# pulseox-v1.net
KiCad netlist of a schematic drawn in EAGLE
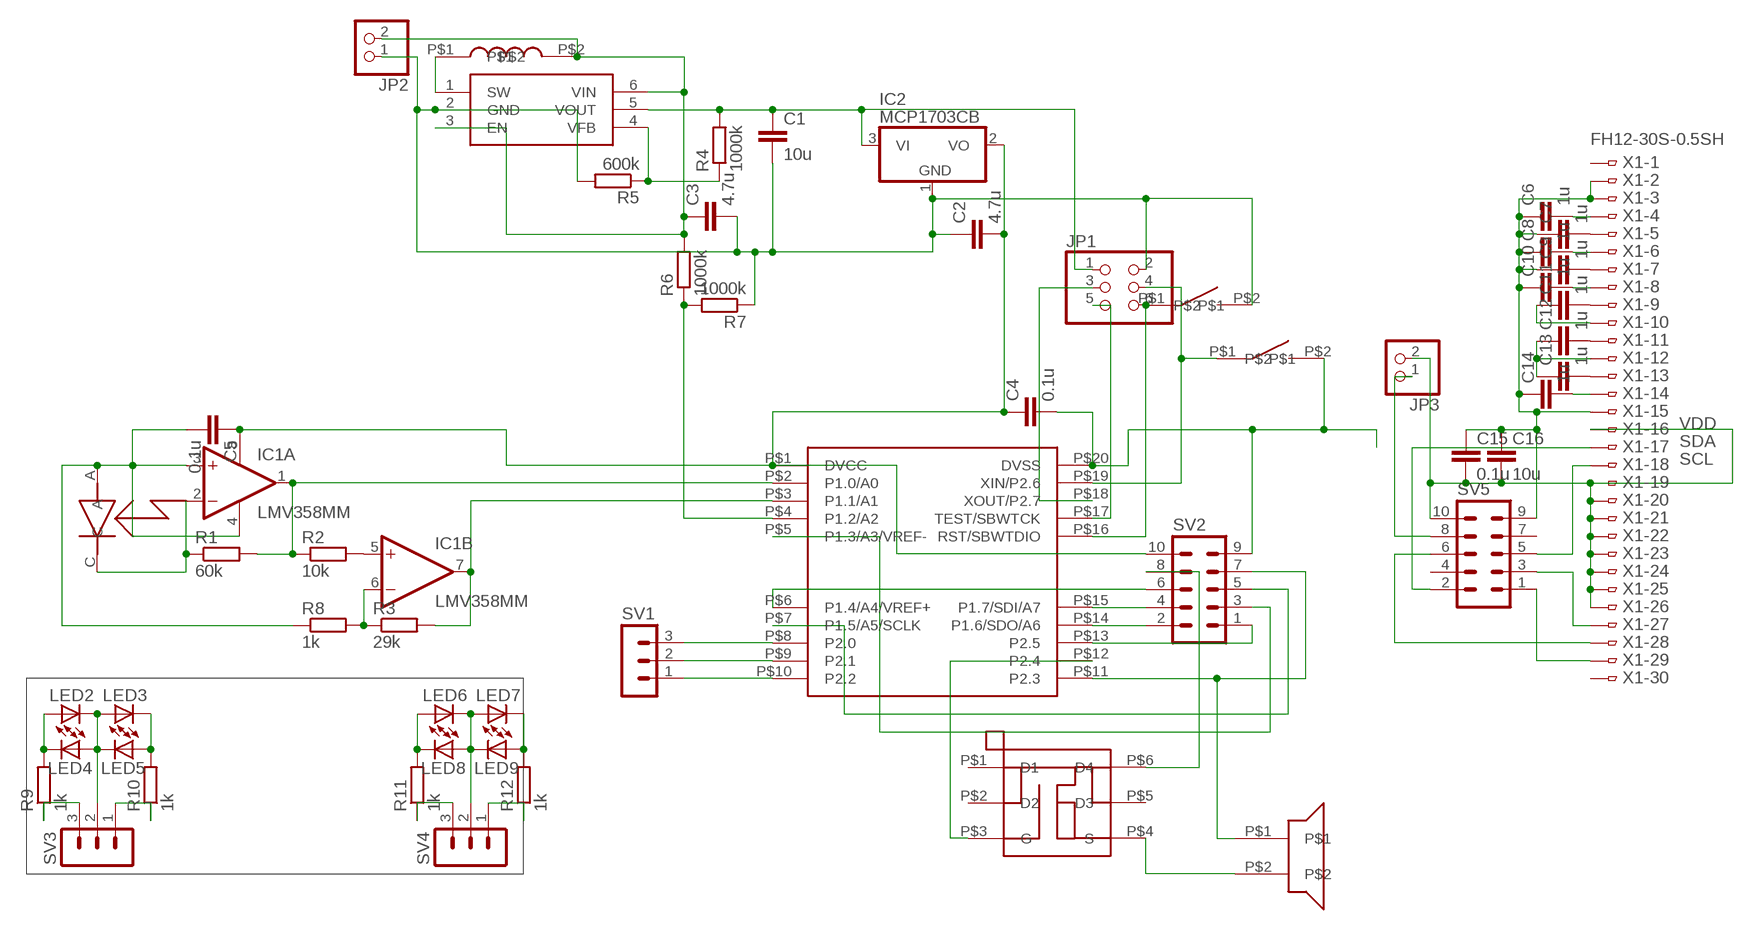
[diagram p0: schematic, sheet 1]

(export (version "E")
  (design (tool "Eeschema 10.0.6"))
  (components
    (comp (ref "C1")
      (value "10u")
      (footprint "eagle-import:C0603K")
      (libsource (lib "eagle-import") (part "C-EUC0603K"))
    )
    (comp (ref "C2")
      (value "4.7u")
      (footprint "eagle-import:C0603K")
      (libsource (lib "eagle-import") (part "C-EUC0603K"))
    )
    (comp (ref "C3")
      (value "4.7u")
      (footprint "eagle-import:C0603K")
      (libsource (lib "eagle-import") (part "C-EUC0603K"))
    )
    (comp (ref "C4")
      (value "0.1u")
      (footprint "eagle-import:C0603K")
      (libsource (lib "eagle-import") (part "C-EUC0603K"))
    )
    (comp (ref "C5")
      (value "0.1u")
      (footprint "eagle-import:C0603K")
      (libsource (lib "eagle-import") (part "C-EUC0603K"))
    )
    (comp (ref "C6")
      (value "1u")
      (footprint "eagle-import:C0603K")
      (libsource (lib "eagle-import") (part "C-EUC0603K"))
    )
    (comp (ref "C7")
      (value "1u")
      (footprint "eagle-import:C0603K")
      (libsource (lib "eagle-import") (part "C-EUC0603K"))
    )
    (comp (ref "C8")
      (value "1u")
      (footprint "eagle-import:C0603K")
      (libsource (lib "eagle-import") (part "C-EUC0603K"))
    )
    (comp (ref "C9")
      (value "1u")
      (footprint "eagle-import:C0603K")
      (libsource (lib "eagle-import") (part "C-EUC0603K"))
    )
    (comp (ref "C10")
      (value "1u")
      (footprint "eagle-import:C0603K")
      (libsource (lib "eagle-import") (part "C-EUC0603K"))
    )
    (comp (ref "C11")
      (value "1u")
      (footprint "eagle-import:C0603K")
      (libsource (lib "eagle-import") (part "C-EUC0603K"))
    )
    (comp (ref "C12")
      (value "1u")
      (footprint "eagle-import:C0603K")
      (libsource (lib "eagle-import") (part "C-EUC0603K"))
    )
    (comp (ref "C13")
      (value "1u")
      (footprint "eagle-import:C0603K")
      (libsource (lib "eagle-import") (part "C-EUC0603K"))
    )
    (comp (ref "C14")
      (value "1u")
      (footprint "eagle-import:C0603K")
      (libsource (lib "eagle-import") (part "C-EUC0603K"))
    )
    (comp (ref "C15")
      (value "0.1u")
      (footprint "eagle-import:C0603K")
      (libsource (lib "eagle-import") (part "C-EUC0603K"))
    )
    (comp (ref "C16")
      (value "10u")
      (footprint "eagle-import:C0603K")
      (libsource (lib "eagle-import") (part "C-EUC0603K"))
    )
    (comp (ref "IC1")
      (value "LMV358MM")
      (footprint "eagle-import:MSOP08")
      (libsource (lib "eagle-import") (part "LMV358?MM"))
    )
    (comp (ref "IC2")
      (value "MCP1703CB")
      (footprint "eagle-import:SOT23")
      (libsource (lib "eagle-import") (part "MCP1703CB"))
    )
    (comp (ref "JP1")
      (value "PINHD-2X3")
      (footprint "eagle-import:2X03")
      (libsource (lib "eagle-import") (part "PINHD-2X3"))
    )
    (comp (ref "JP2")
      (value "PINHD-1X2")
      (footprint "eagle-import:1X02")
      (libsource (lib "eagle-import") (part "PINHD-1X2"))
    )
    (comp (ref "JP3")
      (value "PINHD-1X2")
      (footprint "eagle-import:1X02")
      (libsource (lib "eagle-import") (part "PINHD-1X2"))
    )
    (comp (ref "LED1")
      (value "QSB34ZR")
      (footprint "eagle-import:R-PLCC2")
      (libsource (lib "eagle-import") (part "QSB34ZR"))
    )
    (comp (ref "LED2")
      (value "LEDCHIP-LED0603")
      (footprint "eagle-import:CHIP-LED0603")
      (libsource (lib "eagle-import") (part "LEDCHIP-LED0603"))
    )
    (comp (ref "LED3")
      (value "LEDCHIP-LED0603")
      (footprint "eagle-import:CHIP-LED0603")
      (libsource (lib "eagle-import") (part "LEDCHIP-LED0603"))
    )
    (comp (ref "LED4")
      (value "LEDCHIP-LED0603")
      (footprint "eagle-import:CHIP-LED0603")
      (libsource (lib "eagle-import") (part "LEDCHIP-LED0603"))
    )
    (comp (ref "LED5")
      (value "LEDCHIP-LED0603")
      (footprint "eagle-import:CHIP-LED0603")
      (libsource (lib "eagle-import") (part "LEDCHIP-LED0603"))
    )
    (comp (ref "LED6")
      (value "LEDCHIP-LED0603")
      (footprint "eagle-import:CHIP-LED0603")
      (libsource (lib "eagle-import") (part "LEDCHIP-LED0603"))
    )
    (comp (ref "LED7")
      (value "LEDCHIP-LED0603")
      (footprint "eagle-import:CHIP-LED0603")
      (libsource (lib "eagle-import") (part "LEDCHIP-LED0603"))
    )
    (comp (ref "LED8")
      (value "LEDCHIP-LED0603")
      (footprint "eagle-import:CHIP-LED0603")
      (libsource (lib "eagle-import") (part "LEDCHIP-LED0603"))
    )
    (comp (ref "LED9")
      (value "LEDCHIP-LED0603")
      (footprint "eagle-import:CHIP-LED0603")
      (libsource (lib "eagle-import") (part "LEDCHIP-LED0603"))
    )
    (comp (ref "R1")
      (value "60k")
      (footprint "eagle-import:R0603")
      (libsource (lib "eagle-import") (part "R-EU_R0603"))
    )
    (comp (ref "R2")
      (value "10k")
      (footprint "eagle-import:R0603")
      (libsource (lib "eagle-import") (part "R-EU_R0603"))
    )
    (comp (ref "R3")
      (value "29k")
      (footprint "eagle-import:R0603")
      (libsource (lib "eagle-import") (part "R-EU_R0603"))
    )
    (comp (ref "R4")
      (value "1000k")
      (footprint "eagle-import:R0603")
      (libsource (lib "eagle-import") (part "R-EU_R0603"))
    )
    (comp (ref "R5")
      (value "600k")
      (footprint "eagle-import:R0603")
      (libsource (lib "eagle-import") (part "R-EU_R0603"))
    )
    (comp (ref "R6")
      (value "1000k")
      (footprint "eagle-import:R0603")
      (libsource (lib "eagle-import") (part "R-EU_R0603"))
    )
    (comp (ref "R7")
      (value "1000k")
      (footprint "eagle-import:R0603")
      (libsource (lib "eagle-import") (part "R-EU_R0603"))
    )
    (comp (ref "R8")
      (value "1k")
      (footprint "eagle-import:R0603")
      (libsource (lib "eagle-import") (part "R-EU_R0603"))
    )
    (comp (ref "R9")
      (value "1k")
      (footprint "eagle-import:R0603")
      (libsource (lib "eagle-import") (part "R-EU_R0603"))
    )
    (comp (ref "R10")
      (value "1k")
      (footprint "eagle-import:R0603")
      (libsource (lib "eagle-import") (part "R-EU_R0603"))
    )
    (comp (ref "R11")
      (value "1k")
      (footprint "eagle-import:R0603")
      (libsource (lib "eagle-import") (part "R-EU_R0603"))
    )
    (comp (ref "R12")
      (value "1k")
      (footprint "eagle-import:R0603")
      (libsource (lib "eagle-import") (part "R-EU_R0603"))
    )
    (comp (ref "SV1")
      (value "MA03-1")
      (footprint "eagle-import:MA03-1")
      (libsource (lib "eagle-import") (part "MA03-1"))
    )
    (comp (ref "SV2")
      (value "MA05-2")
      (footprint "eagle-import:MA05-2")
      (libsource (lib "eagle-import") (part "MA05-2"))
    )
    (comp (ref "SV3")
      (value "MA03-1")
      (footprint "eagle-import:MA03-1")
      (libsource (lib "eagle-import") (part "MA03-1"))
    )
    (comp (ref "SV4")
      (value "MA03-1")
      (footprint "eagle-import:MA03-1")
      (libsource (lib "eagle-import") (part "MA03-1"))
    )
    (comp (ref "SV5")
      (value "MA05-2")
      (footprint "eagle-import:MA05-2")
      (libsource (lib "eagle-import") (part "MA05-2"))
    )
    (comp (ref "U$1")
      (value "MSP430G2452IPW20")
      (footprint "eagle-import:TSSOP-20")
      (libsource (lib "eagle-import") (part "MSP430G2452IPW20"))
    )
    (comp (ref "U$2")
      (value "MCP1640SOT23-6")
      (footprint "eagle-import:SOT23-6L")
      (libsource (lib "eagle-import") (part "MCP1640SOT23-6"))
    )
    (comp (ref "U$3")
      (value "WE-TPC")
      (footprint "eagle-import:WE-TPC")
      (libsource (lib "eagle-import") (part "WE-TPC"))
    )
    (comp (ref "U$4")
      (value "BSD816SN")
      (footprint "eagle-import:SOT363")
      (libsource (lib "eagle-import") (part "BSD816SN"))
    )
    (comp (ref "U$5")
      (value "FSMSM")
      (footprint "eagle-import:FSMSM")
      (libsource (lib "eagle-import") (part "FSMSM"))
    )
    (comp (ref "U$6")
      (value "FSMSM")
      (footprint "eagle-import:FSMSM")
      (libsource (lib "eagle-import") (part "FSMSM"))
    )
    (comp (ref "U$7")
      (value "AT-2440-TWT-R")
      (footprint "eagle-import:AT-2440-TWT-R")
      (libsource (lib "eagle-import") (part "AT-2440-TWT-R"))
    )
    (comp (ref "X1")
      (value "FH12-30S-0.5SH")
      (footprint "eagle-import:FH12-30S-0.5SH")
      (fields (field (name "MPN") "FH12-30S-0.5SH(55)"))
      (libsource (lib "eagle-import") (part "FH12-30S-0.5SH"))
    )
  )
  (nets
    (net (code "1") (name "/GND") (class "Default")
      (node (ref "C1") (pin "2") (pinfunction "2_2") (pintype "passive"))
      (node (ref "C2") (pin "1") (pinfunction "1_1") (pintype "passive"))
      (node (ref "C3") (pin "2") (pinfunction "2_2") (pintype "passive"))
      (node (ref "C4") (pin "2") (pinfunction "2_2") (pintype "passive"))
      (node (ref "C5") (pin "2") (pinfunction "2_2") (pintype "passive"))
      (node (ref "IC1") (pin "3") (pinfunction "+IN_3") (pintype "input"))
      (node (ref "IC1") (pin "4") (pinfunction "V-_4") (pintype "power_in"))
      (node (ref "IC2") (pin "1") (pinfunction "GND_1") (pintype "passive"))
      (node (ref "JP1") (pin "2") (pinfunction "2_2") (pintype "passive"))
      (node (ref "JP2") (pin "1") (pinfunction "1_1") (pintype "passive"))
      (node (ref "LED1") (pin "A") (pinfunction "A_A") (pintype "bidirectional"))
      (node (ref "R5") (pin "2") (pinfunction "2_2") (pintype "passive"))
      (node (ref "R7") (pin "1") (pinfunction "1_1") (pintype "passive"))
      (node (ref "R8") (pin "1") (pinfunction "1_1") (pintype "passive"))
      (node (ref "SV2") (pin "9") (pinfunction "9_9") (pintype "passive"))
      (node (ref "U$1") (pin "P$20") (pinfunction "DVSS_P$20") (pintype "bidirectional"))
      (node (ref "U$2") (pin "2") (pinfunction "GND_2") (pintype "bidirectional"))
      (node (ref "U$4") (pin "P$4") (pinfunction "S_P$4") (pintype "bidirectional"))
      (node (ref "U$5") (pin "P$2") (pinfunction "P$2_P$2") (pintype "bidirectional"))
      (node (ref "U$6") (pin "P$2") (pinfunction "P$2_P$2") (pintype "bidirectional"))
      (node (ref "U$7") (pin "P$2") (pinfunction "P$2_P$2") (pintype "bidirectional"))
    )
    (net (code "2") (name "Net-(IC1A--IN)") (class "Default")
      (node (ref "IC1") (pin "2") (pinfunction "-IN_2") (pintype "input"))
      (node (ref "LED1") (pin "C") (pinfunction "C_C") (pintype "bidirectional"))
      (node (ref "R1") (pin "1") (pinfunction "1_1") (pintype "passive"))
    )
    (net (code "3") (name "Net-(IC1A-OUT)") (class "Default")
      (node (ref "IC1") (pin "1") (pinfunction "OUT_1") (pintype "output"))
      (node (ref "R1") (pin "2") (pinfunction "2_2") (pintype "passive"))
      (node (ref "R2") (pin "1") (pinfunction "1_1") (pintype "passive"))
      (node (ref "U$1") (pin "P$2") (pinfunction "P1.0/A0_P$2") (pintype "bidirectional"))
    )
    (net (code "4") (name "Net-(IC1B-+IN)") (class "Default")
      (node (ref "IC1") (pin "5") (pinfunction "+IN_5") (pintype "input"))
      (node (ref "R2") (pin "2") (pinfunction "2_2") (pintype "passive"))
    )
    (net (code "5") (name "Net-(IC1B--IN)") (class "Default")
      (node (ref "IC1") (pin "6") (pinfunction "-IN_6") (pintype "input"))
      (node (ref "R3") (pin "1") (pinfunction "1_1") (pintype "passive"))
      (node (ref "R8") (pin "2") (pinfunction "2_2") (pintype "passive"))
    )
    (net (code "6") (name "Net-(IC1B-OUT)") (class "Default")
      (node (ref "IC1") (pin "7") (pinfunction "OUT_7") (pintype "output"))
      (node (ref "R3") (pin "2") (pinfunction "2_2") (pintype "passive"))
      (node (ref "U$1") (pin "P$3") (pinfunction "P1.1/A1_P$3") (pintype "bidirectional"))
    )
    (net (code "7") (name "Net-(IC1C-V+)") (class "Default")
      (node (ref "C2") (pin "2") (pinfunction "2_2") (pintype "passive"))
      (node (ref "C4") (pin "1") (pinfunction "1_1") (pintype "passive"))
      (node (ref "C5") (pin "1") (pinfunction "1_1") (pintype "passive"))
      (node (ref "IC1") (pin "8") (pinfunction "V+_8") (pintype "power_in"))
      (node (ref "IC2") (pin "2") (pinfunction "VO_2") (pintype "passive"))
      (node (ref "SV2") (pin "10") (pinfunction "10_10") (pintype "passive"))
      (node (ref "U$1") (pin "P$1") (pinfunction "DVCC_P$1") (pintype "bidirectional"))
    )
    (net (code "8") (name "Net-(IC2-VI)") (class "Default")
      (node (ref "C1") (pin "1") (pinfunction "1_1") (pintype "passive"))
      (node (ref "IC2") (pin "3") (pinfunction "VI_3") (pintype "input"))
      (node (ref "JP1") (pin "1") (pinfunction "1_1") (pintype "passive"))
      (node (ref "R4") (pin "2") (pinfunction "2_2") (pintype "passive"))
      (node (ref "U$2") (pin "5") (pinfunction "VOUT_5") (pintype "bidirectional"))
    )
    (net (code "9") (name "Net-(JP3-Pad1)") (class "Default")
      (node (ref "JP3") (pin "1") (pinfunction "1_1") (pintype "passive"))
      (node (ref "SV5") (pin "8") (pinfunction "8_8") (pintype "passive"))
    )
    (net (code "10") (name "Net-(LED2-PadA)") (class "Default")
      (node (ref "LED2") (pin "A") (pinfunction "A_A") (pintype "passive"))
      (node (ref "LED4") (pin "C") (pinfunction "C_C") (pintype "passive"))
      (node (ref "R9") (pin "2") (pinfunction "2_2") (pintype "passive"))
    )
    (net (code "11") (name "Net-(LED2-PadC)") (class "Default")
      (node (ref "LED2") (pin "C") (pinfunction "C_C") (pintype "passive"))
      (node (ref "LED3") (pin "A") (pinfunction "A_A") (pintype "passive"))
      (node (ref "LED4") (pin "A") (pinfunction "A_A") (pintype "passive"))
      (node (ref "LED5") (pin "C") (pinfunction "C_C") (pintype "passive"))
      (node (ref "SV3") (pin "2") (pinfunction "2_2") (pintype "passive"))
    )
    (net (code "12") (name "Net-(LED3-PadC)") (class "Default")
      (node (ref "LED3") (pin "C") (pinfunction "C_C") (pintype "passive"))
      (node (ref "LED5") (pin "A") (pinfunction "A_A") (pintype "passive"))
      (node (ref "R10") (pin "2") (pinfunction "2_2") (pintype "passive"))
    )
    (net (code "13") (name "Net-(LED6-PadA)") (class "Default")
      (node (ref "LED6") (pin "A") (pinfunction "A_A") (pintype "passive"))
      (node (ref "LED8") (pin "C") (pinfunction "C_C") (pintype "passive"))
      (node (ref "R11") (pin "2") (pinfunction "2_2") (pintype "passive"))
    )
    (net (code "14") (name "Net-(LED6-PadC)") (class "Default")
      (node (ref "LED6") (pin "C") (pinfunction "C_C") (pintype "passive"))
      (node (ref "LED7") (pin "A") (pinfunction "A_A") (pintype "passive"))
      (node (ref "LED8") (pin "A") (pinfunction "A_A") (pintype "passive"))
      (node (ref "LED9") (pin "C") (pinfunction "C_C") (pintype "passive"))
      (node (ref "SV4") (pin "2") (pinfunction "2_2") (pintype "passive"))
    )
    (net (code "15") (name "Net-(LED7-PadC)") (class "Default")
      (node (ref "LED7") (pin "C") (pinfunction "C_C") (pintype "passive"))
      (node (ref "LED9") (pin "A") (pinfunction "A_A") (pintype "passive"))
      (node (ref "R12") (pin "2") (pinfunction "2_2") (pintype "passive"))
    )
    (net (code "16") (name "Net-(R9-Pad1)") (class "Default")
      (node (ref "R9") (pin "1") (pinfunction "1_1") (pintype "passive"))
      (node (ref "SV3") (pin "3") (pinfunction "3_3") (pintype "passive"))
    )
    (net (code "17") (name "Net-(R10-Pad1)") (class "Default")
      (node (ref "R10") (pin "1") (pinfunction "1_1") (pintype "passive"))
      (node (ref "SV3") (pin "1") (pinfunction "1_1") (pintype "passive"))
    )
    (net (code "18") (name "Net-(R11-Pad1)") (class "Default")
      (node (ref "R11") (pin "1") (pinfunction "1_1") (pintype "passive"))
      (node (ref "SV4") (pin "3") (pinfunction "3_3") (pintype "passive"))
    )
    (net (code "19") (name "Net-(R12-Pad1)") (class "Default")
      (node (ref "R12") (pin "1") (pinfunction "1_1") (pintype "passive"))
      (node (ref "SV4") (pin "1") (pinfunction "1_1") (pintype "passive"))
    )
    (net (code "20") (name "Net-(U$1-P1.2{slash}A2)") (class "Default")
      (node (ref "R6") (pin "1") (pinfunction "1_1") (pintype "passive"))
      (node (ref "R7") (pin "2") (pinfunction "2_2") (pintype "passive"))
      (node (ref "U$1") (pin "P$4") (pinfunction "P1.2/A2_P$4") (pintype "bidirectional"))
    )
    (net (code "21") (name "Net-(U$1-P1.3{slash}A3{slash}VREF-)") (class "Default")
      (node (ref "SV2") (pin "3") (pinfunction "3_3") (pintype "passive"))
      (node (ref "U$1") (pin "P$5") (pinfunction "P1.3/A3/VREF-_P$5") (pintype "bidirectional"))
    )
    (net (code "22") (name "Net-(U$1-P1.4{slash}A4{slash}VREF+)") (class "Default")
      (node (ref "SV2") (pin "6") (pinfunction "6_6") (pintype "passive"))
      (node (ref "U$1") (pin "P$6") (pinfunction "P1.4/A4/VREF+_P$6") (pintype "bidirectional"))
    )
    (net (code "23") (name "Net-(U$1-P1.5{slash}A5{slash}SCLK)") (class "Default")
      (node (ref "SV2") (pin "5") (pinfunction "5_5") (pintype "passive"))
      (node (ref "U$1") (pin "P$7") (pinfunction "P1.5/A5/SCLK_P$7") (pintype "bidirectional"))
    )
    (net (code "24") (name "Net-(U$1-P1.6{slash}SDO{slash}A6)") (class "Default")
      (node (ref "SV2") (pin "2") (pinfunction "2_2") (pintype "passive"))
      (node (ref "U$1") (pin "P$14") (pinfunction "P1.6/SDO/A6_P$14") (pintype "bidirectional"))
    )
    (net (code "25") (name "Net-(U$1-P1.7{slash}SDI{slash}A7)") (class "Default")
      (node (ref "SV2") (pin "4") (pinfunction "4_4") (pintype "passive"))
      (node (ref "U$1") (pin "P$15") (pinfunction "P1.7/SDI/A7_P$15") (pintype "bidirectional"))
    )
    (net (code "26") (name "Net-(U$1-P2.0)") (class "Default")
      (node (ref "SV1") (pin "3") (pinfunction "3_3") (pintype "passive"))
      (node (ref "U$1") (pin "P$8") (pinfunction "P2.0_P$8") (pintype "bidirectional"))
    )
    (net (code "27") (name "Net-(U$1-P2.1)") (class "Default")
      (node (ref "SV1") (pin "2") (pinfunction "2_2") (pintype "passive"))
      (node (ref "U$1") (pin "P$9") (pinfunction "P2.1_P$9") (pintype "bidirectional"))
    )
    (net (code "28") (name "Net-(U$1-P2.2)") (class "Default")
      (node (ref "SV1") (pin "1") (pinfunction "1_1") (pintype "passive"))
      (node (ref "U$1") (pin "P$10") (pinfunction "P2.2_P$10") (pintype "bidirectional"))
    )
    (net (code "29") (name "Net-(U$1-P2.3)") (class "Default")
      (node (ref "SV2") (pin "7") (pinfunction "7_7") (pintype "passive"))
      (node (ref "U$1") (pin "P$11") (pinfunction "P2.3_P$11") (pintype "bidirectional"))
      (node (ref "U$7") (pin "P$1") (pinfunction "P$1_P$1") (pintype "bidirectional"))
    )
    (net (code "30") (name "Net-(U$1-P2.4)") (class "Default")
      (node (ref "U$1") (pin "P$12") (pinfunction "P2.4_P$12") (pintype "bidirectional"))
      (node (ref "U$4") (pin "P$3") (pinfunction "G_P$3") (pintype "bidirectional"))
    )
    (net (code "31") (name "Net-(U$1-P2.5)") (class "Default")
      (node (ref "SV2") (pin "1") (pinfunction "1_1") (pintype "passive"))
      (node (ref "U$1") (pin "P$13") (pinfunction "P2.5_P$13") (pintype "bidirectional"))
    )
    (net (code "32") (name "Net-(U$1-RST{slash}SBWTDIO)") (class "Default")
      (node (ref "JP1") (pin "6") (pinfunction "6_6") (pintype "passive"))
      (node (ref "U$1") (pin "P$16") (pinfunction "RST/SBWTDIO_P$16") (pintype "bidirectional"))
      (node (ref "U$5") (pin "P$1") (pinfunction "P$1_P$1") (pintype "bidirectional"))
    )
    (net (code "33") (name "Net-(U$1-TEST{slash}SBWTCK)") (class "Default")
      (node (ref "JP1") (pin "5") (pinfunction "5_5") (pintype "passive"))
      (node (ref "U$1") (pin "P$17") (pinfunction "TEST/SBWTCK_P$17") (pintype "bidirectional"))
    )
    (net (code "34") (name "Net-(U$1-XIN{slash}P2.6)") (class "Default")
      (node (ref "JP1") (pin "4") (pinfunction "4_4") (pintype "passive"))
      (node (ref "U$1") (pin "P$19") (pinfunction "XIN/P2.6_P$19") (pintype "bidirectional"))
      (node (ref "U$6") (pin "P$1") (pinfunction "P$1_P$1") (pintype "bidirectional"))
    )
    (net (code "35") (name "Net-(U$1-XOUT{slash}P2.7)") (class "Default")
      (node (ref "JP1") (pin "3") (pinfunction "3_3") (pintype "passive"))
      (node (ref "U$1") (pin "P$18") (pinfunction "XOUT/P2.7_P$18") (pintype "bidirectional"))
    )
    (net (code "36") (name "Net-(U$2-EN)") (class "Default")
      (node (ref "C3") (pin "1") (pinfunction "1_1") (pintype "passive"))
      (node (ref "JP2") (pin "2") (pinfunction "2_2") (pintype "passive"))
      (node (ref "R6") (pin "2") (pinfunction "2_2") (pintype "passive"))
      (node (ref "U$2") (pin "3") (pinfunction "EN_3") (pintype "bidirectional"))
      (node (ref "U$2") (pin "6") (pinfunction "VIN_6") (pintype "bidirectional"))
      (node (ref "U$3") (pin "P$2") (pinfunction "P$2_P$2") (pintype "bidirectional"))
    )
    (net (code "37") (name "Net-(U$2-SW)") (class "Default")
      (node (ref "U$2") (pin "1") (pinfunction "SW_1") (pintype "bidirectional"))
      (node (ref "U$3") (pin "P$1") (pinfunction "P$1_P$1") (pintype "bidirectional"))
    )
    (net (code "38") (name "Net-(U$2-VFB)") (class "Default")
      (node (ref "R4") (pin "1") (pinfunction "1_1") (pintype "passive"))
      (node (ref "R5") (pin "1") (pinfunction "1_1") (pintype "passive"))
      (node (ref "U$2") (pin "4") (pinfunction "VFB_4") (pintype "bidirectional"))
    )
    (net (code "39") (name "Net-(U$4-D4)") (class "Default")
      (node (ref "SV2") (pin "8") (pinfunction "8_8") (pintype "passive"))
      (node (ref "U$4") (pin "P$6") (pinfunction "D4_P$6") (pintype "bidirectional"))
    )
    (net (code "40") (name "Net-(X1AA-1)") (class "Default")
      (node (ref "C8") (pin "2") (pinfunction "2_2") (pintype "passive"))
      (node (ref "X1") (pin "6") (pinfunction "1_6") (pintype "passive"))
    )
    (net (code "41") (name "Net-(X1AB-1)") (class "Default")
      (node (ref "C9") (pin "2") (pinfunction "2_2") (pintype "passive"))
      (node (ref "X1") (pin "7") (pinfunction "1_7") (pintype "passive"))
    )
    (net (code "42") (name "Net-(X1AC-1)") (class "Default")
      (node (ref "C10") (pin "2") (pinfunction "2_2") (pintype "passive"))
      (node (ref "X1") (pin "8") (pinfunction "1_8") (pintype "passive"))
    )
    (net (code "43") (name "Net-(X1AD-1)") (class "Default")
      (node (ref "C11") (pin "2") (pinfunction "2_2") (pintype "passive"))
      (node (ref "X1") (pin "9") (pinfunction "1_9") (pintype "passive"))
    )
    (net (code "44") (name "Net-(X1B-1)") (class "Default")
      (node (ref "C11") (pin "1") (pinfunction "1_1") (pintype "passive"))
      (node (ref "X1") (pin "10") (pinfunction "1_10") (pintype "passive"))
    )
    (net (code "45") (name "Net-(X1C-1)") (class "Default")
      (node (ref "C12") (pin "2") (pinfunction "2_2") (pintype "passive"))
      (node (ref "X1") (pin "11") (pinfunction "1_11") (pintype "passive"))
    )
    (net (code "46") (name "Net-(X1D-1)") (class "Default")
      (node (ref "C12") (pin "1") (pinfunction "1_1") (pintype "passive"))
      (node (ref "C13") (pin "1") (pinfunction "1_1") (pintype "passive"))
      (node (ref "X1") (pin "12") (pinfunction "1_12") (pintype "passive"))
    )
    (net (code "47") (name "Net-(X1E-1)") (class "Default")
      (node (ref "C13") (pin "2") (pinfunction "2_2") (pintype "passive"))
      (node (ref "X1") (pin "13") (pinfunction "1_13") (pintype "passive"))
    )
    (net (code "48") (name "Net-(X1F-1)") (class "Default")
      (node (ref "C14") (pin "2") (pinfunction "2_2") (pintype "passive"))
      (node (ref "X1") (pin "14") (pinfunction "1_14") (pintype "passive"))
    )
    (net (code "49") (name "Net-(X1G-1)") (class "Default")
      (node (ref "C10") (pin "1") (pinfunction "1_1") (pintype "passive"))
      (node (ref "C14") (pin "1") (pinfunction "1_1") (pintype "passive"))
      (node (ref "C15") (pin "1") (pinfunction "1_1") (pintype "passive"))
      (node (ref "C16") (pin "1") (pinfunction "1_1") (pintype "passive"))
      (node (ref "C6") (pin "1") (pinfunction "1_1") (pintype "passive"))
      (node (ref "C7") (pin "1") (pinfunction "1_1") (pintype "passive"))
      (node (ref "C8") (pin "1") (pinfunction "1_1") (pintype "passive"))
      (node (ref "C9") (pin "1") (pinfunction "1_1") (pintype "passive"))
      (node (ref "SV5") (pin "9") (pinfunction "9_9") (pintype "passive"))
      (node (ref "X1") (pin "15") (pinfunction "1_15") (pintype "passive"))
      (node (ref "X1") (pin "2") (pinfunction "1_2") (pintype "passive"))
      (node (ref "X1") (pin "3") (pinfunction "1_3") (pintype "passive"))
    )
    (net (code "50") (name "Net-(X1H-1)") (class "Default")
      (node (ref "C15") (pin "2") (pinfunction "2_2") (pintype "passive"))
      (node (ref "C16") (pin "2") (pinfunction "2_2") (pintype "passive"))
      (node (ref "JP3") (pin "2") (pinfunction "2_2") (pintype "passive"))
      (node (ref "SV5") (pin "10") (pinfunction "10_10") (pintype "passive"))
      (node (ref "X1") (pin "16") (pinfunction "1_16") (pintype "passive"))
      (node (ref "X1") (pin "19") (pinfunction "1_19") (pintype "passive"))
      (node (ref "X1") (pin "20") (pinfunction "1_20") (pintype "passive"))
      (node (ref "X1") (pin "21") (pinfunction "1_21") (pintype "passive"))
      (node (ref "X1") (pin "22") (pinfunction "1_22") (pintype "passive"))
      (node (ref "X1") (pin "23") (pinfunction "1_23") (pintype "passive"))
      (node (ref "X1") (pin "24") (pinfunction "1_24") (pintype "passive"))
      (node (ref "X1") (pin "25") (pinfunction "1_25") (pintype "passive"))
      (node (ref "X1") (pin "26") (pinfunction "1_26") (pintype "passive"))
    )
    (net (code "51") (name "Net-(X1I-1)") (class "Default")
      (node (ref "SV5") (pin "2") (pinfunction "2_2") (pintype "passive"))
      (node (ref "X1") (pin "17") (pinfunction "1_17") (pintype "passive"))
    )
    (net (code "52") (name "Net-(X1J-1)") (class "Default")
      (node (ref "SV5") (pin "5") (pinfunction "5_5") (pintype "passive"))
      (node (ref "X1") (pin "18") (pinfunction "1_18") (pintype "passive"))
    )
    (net (code "53") (name "Net-(X1T-1)") (class "Default")
      (node (ref "SV5") (pin "3") (pinfunction "3_3") (pintype "passive"))
      (node (ref "X1") (pin "27") (pinfunction "1_27") (pintype "passive"))
    )
    (net (code "54") (name "Net-(X1U-1)") (class "Default")
      (node (ref "SV5") (pin "6") (pinfunction "6_6") (pintype "passive"))
      (node (ref "X1") (pin "28") (pinfunction "1_28") (pintype "passive"))
    )
    (net (code "55") (name "Net-(X1V-1)") (class "Default")
      (node (ref "SV5") (pin "1") (pinfunction "1_1") (pintype "passive"))
      (node (ref "X1") (pin "29") (pinfunction "1_29") (pintype "passive"))
    )
    (net (code "56") (name "Net-(X1Y-1)") (class "Default")
      (node (ref "C6") (pin "2") (pinfunction "2_2") (pintype "passive"))
      (node (ref "X1") (pin "4") (pinfunction "1_4") (pintype "passive"))
    )
    (net (code "57") (name "Net-(X1Z-1)") (class "Default")
      (node (ref "C7") (pin "2") (pinfunction "2_2") (pintype "passive"))
      (node (ref "X1") (pin "5") (pinfunction "1_5") (pintype "passive"))
    )
    (net (code "58") (name "unconnected-(SV5-Pad4)") (class "Default")
      (node (ref "SV5") (pin "4") (pinfunction "4_4") (pintype "passive"))
    )
    (net (code "59") (name "unconnected-(SV5-Pad7)") (class "Default")
      (node (ref "SV5") (pin "7") (pinfunction "7_7") (pintype "passive"))
    )
    (net (code "60") (name "unconnected-(U$4-D1-PadP$1)") (class "Default")
      (node (ref "U$4") (pin "P$1") (pinfunction "D1_P$1") (pintype "bidirectional"))
    )
    (net (code "61") (name "unconnected-(U$4-D2-PadP$2)") (class "Default")
      (node (ref "U$4") (pin "P$2") (pinfunction "D2_P$2") (pintype "bidirectional"))
    )
    (net (code "62") (name "unconnected-(U$4-D3-PadP$5)") (class "Default")
      (node (ref "U$4") (pin "P$5") (pinfunction "D3_P$5") (pintype "bidirectional"))
    )
    (net (code "63") (name "unconnected-(X1-Pad1)") (class "Default")
      (node (ref "X1") (pin "1") (pinfunction "1_1") (pintype "passive"))
    )
    (net (code "64") (name "unconnected-(X1X-1-Pad30)") (class "Default")
      (node (ref "X1") (pin "30") (pinfunction "1_30") (pintype "passive"))
    )
  )
)
